# TPT02r.net
KiCad netlist of a schematic drawn in EAGLE
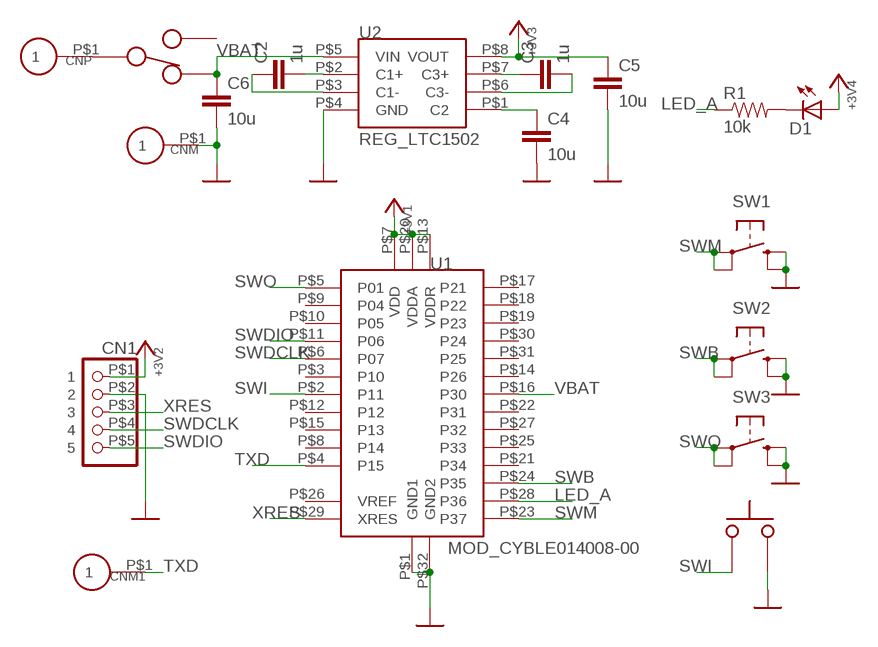
[diagram p0: schematic, sheet 1]

(export (version "E")
  (design (tool "Eeschema 10.0.6"))
  (components
    (comp (ref "C2")
      (value "1u")
      (footprint "eagle-import:0603")
      (libsource (lib "eagle-import") (part "CAP0603"))
    )
    (comp (ref "C3")
      (value "1u")
      (footprint "eagle-import:0603")
      (libsource (lib "eagle-import") (part "CAP0603"))
    )
    (comp (ref "C4")
      (value "10u")
      (footprint "eagle-import:0603")
      (libsource (lib "eagle-import") (part "CAP0603"))
    )
    (comp (ref "C5")
      (value "10u")
      (footprint "eagle-import:0603")
      (libsource (lib "eagle-import") (part "CAP0603"))
    )
    (comp (ref "C6")
      (value "10u")
      (footprint "eagle-import:0603")
      (libsource (lib "eagle-import") (part "CAP0603"))
    )
    (comp (ref "CN1")
      (value "CON_PINHD-1X550MIL")
      (footprint "eagle-import:1X5_50MIL")
      (libsource (lib "eagle-import") (part "CON_PINHD-1X550MIL"))
    )
    (comp (ref "CNM")
      (value "CON_P01SMD1MM")
      (footprint "eagle-import:PAD_SMD1MM")
      (libsource (lib "eagle-import") (part "CON_P01SMD1MM"))
    )
    (comp (ref "CNM1")
      (value "CON_P01SMD1MM")
      (footprint "eagle-import:PAD_SMD1MM")
      (libsource (lib "eagle-import") (part "CON_P01SMD1MM"))
    )
    (comp (ref "CNP")
      (value "CON_P01SMD1MM")
      (footprint "eagle-import:PAD_SMD1MM")
      (libsource (lib "eagle-import") (part "CON_P01SMD1MM"))
    )
    (comp (ref "D1")
      (value "LED0603")
      (footprint "eagle-import:SPARKFUN_LED-0603")
      (libsource (lib "eagle-import") (part "LED0603"))
    )
    (comp (ref "R1")
      (value "10k")
      (footprint "eagle-import:0603")
      (libsource (lib "eagle-import") (part "RES0603"))
    )
    (comp (ref "SW1")
      (value "SW_TACTEVQP2")
      (footprint "eagle-import:SW_EVQP2")
      (libsource (lib "eagle-import") (part "SW_TACTEVQP2"))
    )
    (comp (ref "SW2")
      (value "SW_TACTTVAF17")
      (footprint "eagle-import:SW_TVAF17")
      (libsource (lib "eagle-import") (part "SW_TACTTVAF17"))
    )
    (comp (ref "SW3")
      (value "SW_TACTTVAF17")
      (footprint "eagle-import:SW_TVAF17")
      (libsource (lib "eagle-import") (part "SW_TACTTVAF17"))
    )
    (comp (ref "SW4")
      (value "SW_SLIDECUS12")
      (footprint "eagle-import:SW_CUS-12")
      (libsource (lib "eagle-import") (part "SW_SLIDECUS12"))
    )
    (comp (ref "SW6")
      (value "SW_TACT2PB3U3000")
      (footprint "eagle-import:SW_B3U-3000P")
      (libsource (lib "eagle-import") (part "SW_TACT2PB3U3000"))
    )
    (comp (ref "U1")
      (value "MOD_CYBLE014008-00")
      (footprint "eagle-import:MOD_CYBLE014008-00")
      (libsource (lib "eagle-import") (part "MOD_CYBLE014008-00"))
    )
    (comp (ref "U2")
      (value "REG_LTC1502")
      (footprint "eagle-import:MSOP8")
      (libsource (lib "eagle-import") (part "REG_LTC1502"))
    )
  )
  (nets
    (net (code "1") (name "/LED_A") (class "Default")
      (node (ref "R1") (pin "1") (pinfunction "1_1") (pintype "passive"))
      (node (ref "U1") (pin "P$28") (pinfunction "P36_P$28") (pintype "bidirectional"))
    )
    (net (code "2") (name "/P$3") (class "Default")
      (node (ref "SW4") (pin "P$3") (pinfunction "P$3_P$3") (pintype "power_in"))
    )
    (net (code "3") (name "/SWB") (class "Default")
      (node (ref "SW2") (pin "P$1") (pinfunction "P_P$1") (pintype "passive"))
      (node (ref "SW2") (pin "P$2") (pinfunction "P1_P$2") (pintype "passive"))
      (node (ref "U1") (pin "P$24") (pinfunction "P35_P$24") (pintype "bidirectional"))
    )
    (net (code "4") (name "/SWDCLK") (class "Default")
      (node (ref "CN1") (pin "P$4") (pinfunction "4_P$4") (pintype "passive"))
      (node (ref "U1") (pin "P$6") (pinfunction "P07_P$6") (pintype "bidirectional"))
    )
    (net (code "5") (name "/SWDIO") (class "Default")
      (node (ref "CN1") (pin "P$5") (pinfunction "5_P$5") (pintype "passive"))
      (node (ref "U1") (pin "P$11") (pinfunction "P06_P$11") (pintype "bidirectional"))
    )
    (net (code "6") (name "/SWI") (class "Default")
      (node (ref "SW6") (pin "P$2") (pinfunction "P$2_P$2") (pintype "passive"))
      (node (ref "U1") (pin "P$2") (pinfunction "P11_P$2") (pintype "bidirectional"))
    )
    (net (code "7") (name "/SWM") (class "Default")
      (node (ref "SW1") (pin "PA1") (pinfunction "P_PA1") (pintype "passive"))
      (node (ref "SW1") (pin "PA2") (pinfunction "P1_PA2") (pintype "passive"))
      (node (ref "U1") (pin "P$23") (pinfunction "P37_P$23") (pintype "bidirectional"))
    )
    (net (code "8") (name "/SWO") (class "Default")
      (node (ref "SW3") (pin "P$1") (pinfunction "P_P$1") (pintype "passive"))
      (node (ref "SW3") (pin "P$2") (pinfunction "P1_P$2") (pintype "passive"))
      (node (ref "U1") (pin "P$5") (pinfunction "P01_P$5") (pintype "bidirectional"))
    )
    (net (code "9") (name "/TXD") (class "Default")
      (node (ref "CNM1") (pin "P$1") (pinfunction "1_P$1") (pintype "bidirectional"))
      (node (ref "U1") (pin "P$4") (pinfunction "P15_P$4") (pintype "bidirectional"))
    )
    (net (code "10") (name "/VBAT") (class "Default")
      (node (ref "C6") (pin "1") (pinfunction "1_1") (pintype "passive"))
      (node (ref "SW4") (pin "P$1") (pinfunction "P$1_P$1") (pintype "power_in"))
      (node (ref "U1") (pin "P$16") (pinfunction "P30_P$16") (pintype "bidirectional"))
      (node (ref "U2") (pin "P$5") (pinfunction "VIN_P$5") (pintype "bidirectional"))
    )
    (net (code "11") (name "/XRES") (class "Default")
      (node (ref "CN1") (pin "P$3") (pinfunction "3_P$3") (pintype "passive"))
      (node (ref "U1") (pin "P$29") (pinfunction "XRES_P$29") (pintype "bidirectional"))
    )
    (net (code "12") (name "Net-(CNP-1)") (class "Default")
      (node (ref "CNP") (pin "P$1") (pinfunction "1_P$1") (pintype "bidirectional"))
      (node (ref "SW4") (pin "P$2") (pinfunction "P$2_P$2") (pintype "power_in"))
    )
    (net (code "13") (name "Net-(D1-PadC)") (class "Default")
      (node (ref "D1") (pin "C") (pinfunction "C_C") (pintype "passive"))
      (node (ref "R1") (pin "2") (pinfunction "2_2") (pintype "passive"))
    )
    (net (code "14") (name "Net-(U2-C1+)") (class "Default")
      (node (ref "C2") (pin "2") (pinfunction "2_2") (pintype "passive"))
      (node (ref "U2") (pin "P$2") (pinfunction "C1+_P$2") (pintype "bidirectional"))
    )
    (net (code "15") (name "Net-(U2-C1-)") (class "Default")
      (node (ref "C2") (pin "1") (pinfunction "1_1") (pintype "passive"))
      (node (ref "U2") (pin "P$3") (pinfunction "C1-_P$3") (pintype "bidirectional"))
    )
    (net (code "16") (name "Net-(U2-C2)") (class "Default")
      (node (ref "C4") (pin "1") (pinfunction "1_1") (pintype "passive"))
      (node (ref "U2") (pin "P$1") (pinfunction "C2_P$1") (pintype "bidirectional"))
    )
    (net (code "17") (name "Net-(U2-C3+)") (class "Default")
      (node (ref "C3") (pin "1") (pinfunction "1_1") (pintype "passive"))
      (node (ref "U2") (pin "P$7") (pinfunction "C3+_P$7") (pintype "bidirectional"))
    )
    (net (code "18") (name "Net-(U2-C3-)") (class "Default")
      (node (ref "C3") (pin "2") (pinfunction "2_2") (pintype "passive"))
      (node (ref "U2") (pin "P$6") (pinfunction "C3-_P$6") (pintype "bidirectional"))
    )
    (net (code "19") (name "POW_+3V3") (class "Default")
      (node (ref "C5") (pin "1") (pinfunction "1_1") (pintype "passive"))
      (node (ref "CN1") (pin "P$1") (pinfunction "1_P$1") (pintype "passive"))
      (node (ref "D1") (pin "A") (pinfunction "A_A") (pintype "passive"))
      (node (ref "U1") (pin "P$13") (pinfunction "VDDR_P$13") (pintype "bidirectional"))
      (node (ref "U1") (pin "P$20") (pinfunction "VDDA_P$20") (pintype "bidirectional"))
      (node (ref "U1") (pin "P$7") (pinfunction "VDD_P$7") (pintype "bidirectional"))
      (node (ref "U2") (pin "P$8") (pinfunction "VOUT_P$8") (pintype "bidirectional"))
    )
    (net (code "20") (name "POW_GND") (class "Default")
      (node (ref "C4") (pin "2") (pinfunction "2_2") (pintype "passive"))
      (node (ref "C5") (pin "2") (pinfunction "2_2") (pintype "passive"))
      (node (ref "C6") (pin "2") (pinfunction "2_2") (pintype "passive"))
      (node (ref "CN1") (pin "P$2") (pinfunction "2_P$2") (pintype "passive"))
      (node (ref "CNM") (pin "P$1") (pinfunction "1_P$1") (pintype "bidirectional"))
      (node (ref "SW1") (pin "PB1") (pinfunction "S_PB1") (pintype "passive"))
      (node (ref "SW1") (pin "PB2") (pinfunction "S1_PB2") (pintype "passive"))
      (node (ref "SW2") (pin "P$3") (pinfunction "S_P$3") (pintype "passive"))
      (node (ref "SW2") (pin "P$4") (pinfunction "S1_P$4") (pintype "passive"))
      (node (ref "SW3") (pin "P$3") (pinfunction "S_P$3") (pintype "passive"))
      (node (ref "SW3") (pin "P$4") (pinfunction "S1_P$4") (pintype "passive"))
      (node (ref "SW6") (pin "P$1") (pinfunction "P$1_P$1") (pintype "passive"))
      (node (ref "U1") (pin "P$1") (pinfunction "GND1_P$1") (pintype "bidirectional"))
      (node (ref "U1") (pin "P$32") (pinfunction "GND2_P$32") (pintype "bidirectional"))
      (node (ref "U2") (pin "P$4") (pinfunction "GND_P$4") (pintype "bidirectional"))
    )
    (net (code "21") (name "unconnected-(U1-P04-PadP$9)") (class "Default")
      (node (ref "U1") (pin "P$9") (pinfunction "P04_P$9") (pintype "bidirectional"))
    )
    (net (code "22") (name "unconnected-(U1-P05-PadP$10)") (class "Default")
      (node (ref "U1") (pin "P$10") (pinfunction "P05_P$10") (pintype "bidirectional"))
    )
    (net (code "23") (name "unconnected-(U1-P10-PadP$3)") (class "Default")
      (node (ref "U1") (pin "P$3") (pinfunction "P10_P$3") (pintype "bidirectional"))
    )
    (net (code "24") (name "unconnected-(U1-P12-PadP$12)") (class "Default")
      (node (ref "U1") (pin "P$12") (pinfunction "P12_P$12") (pintype "bidirectional"))
    )
    (net (code "25") (name "unconnected-(U1-P13-PadP$15)") (class "Default")
      (node (ref "U1") (pin "P$15") (pinfunction "P13_P$15") (pintype "bidirectional"))
    )
    (net (code "26") (name "unconnected-(U1-P14-PadP$8)") (class "Default")
      (node (ref "U1") (pin "P$8") (pinfunction "P14_P$8") (pintype "bidirectional"))
    )
    (net (code "27") (name "unconnected-(U1-P21-PadP$17)") (class "Default")
      (node (ref "U1") (pin "P$17") (pinfunction "P21_P$17") (pintype "bidirectional"))
    )
    (net (code "28") (name "unconnected-(U1-P22-PadP$18)") (class "Default")
      (node (ref "U1") (pin "P$18") (pinfunction "P22_P$18") (pintype "bidirectional"))
    )
    (net (code "29") (name "unconnected-(U1-P23-PadP$19)") (class "Default")
      (node (ref "U1") (pin "P$19") (pinfunction "P23_P$19") (pintype "bidirectional"))
    )
    (net (code "30") (name "unconnected-(U1-P24-PadP$30)") (class "Default")
      (node (ref "U1") (pin "P$30") (pinfunction "P24_P$30") (pintype "bidirectional"))
    )
    (net (code "31") (name "unconnected-(U1-P25-PadP$31)") (class "Default")
      (node (ref "U1") (pin "P$31") (pinfunction "P25_P$31") (pintype "bidirectional"))
    )
    (net (code "32") (name "unconnected-(U1-P26-PadP$14)") (class "Default")
      (node (ref "U1") (pin "P$14") (pinfunction "P26_P$14") (pintype "bidirectional"))
    )
    (net (code "33") (name "unconnected-(U1-P31-PadP$22)") (class "Default")
      (node (ref "U1") (pin "P$22") (pinfunction "P31_P$22") (pintype "bidirectional"))
    )
    (net (code "34") (name "unconnected-(U1-P32-PadP$27)") (class "Default")
      (node (ref "U1") (pin "P$27") (pinfunction "P32_P$27") (pintype "bidirectional"))
    )
    (net (code "35") (name "unconnected-(U1-P33-PadP$25)") (class "Default")
      (node (ref "U1") (pin "P$25") (pinfunction "P33_P$25") (pintype "bidirectional"))
    )
    (net (code "36") (name "unconnected-(U1-P34-PadP$21)") (class "Default")
      (node (ref "U1") (pin "P$21") (pinfunction "P34_P$21") (pintype "bidirectional"))
    )
    (net (code "37") (name "unconnected-(U1-VREF-PadP$26)") (class "Default")
      (node (ref "U1") (pin "P$26") (pinfunction "VREF_P$26") (pintype "bidirectional"))
    )
  )
)
